# line_kick.net
KiCad netlist of a schematic drawn in EAGLE
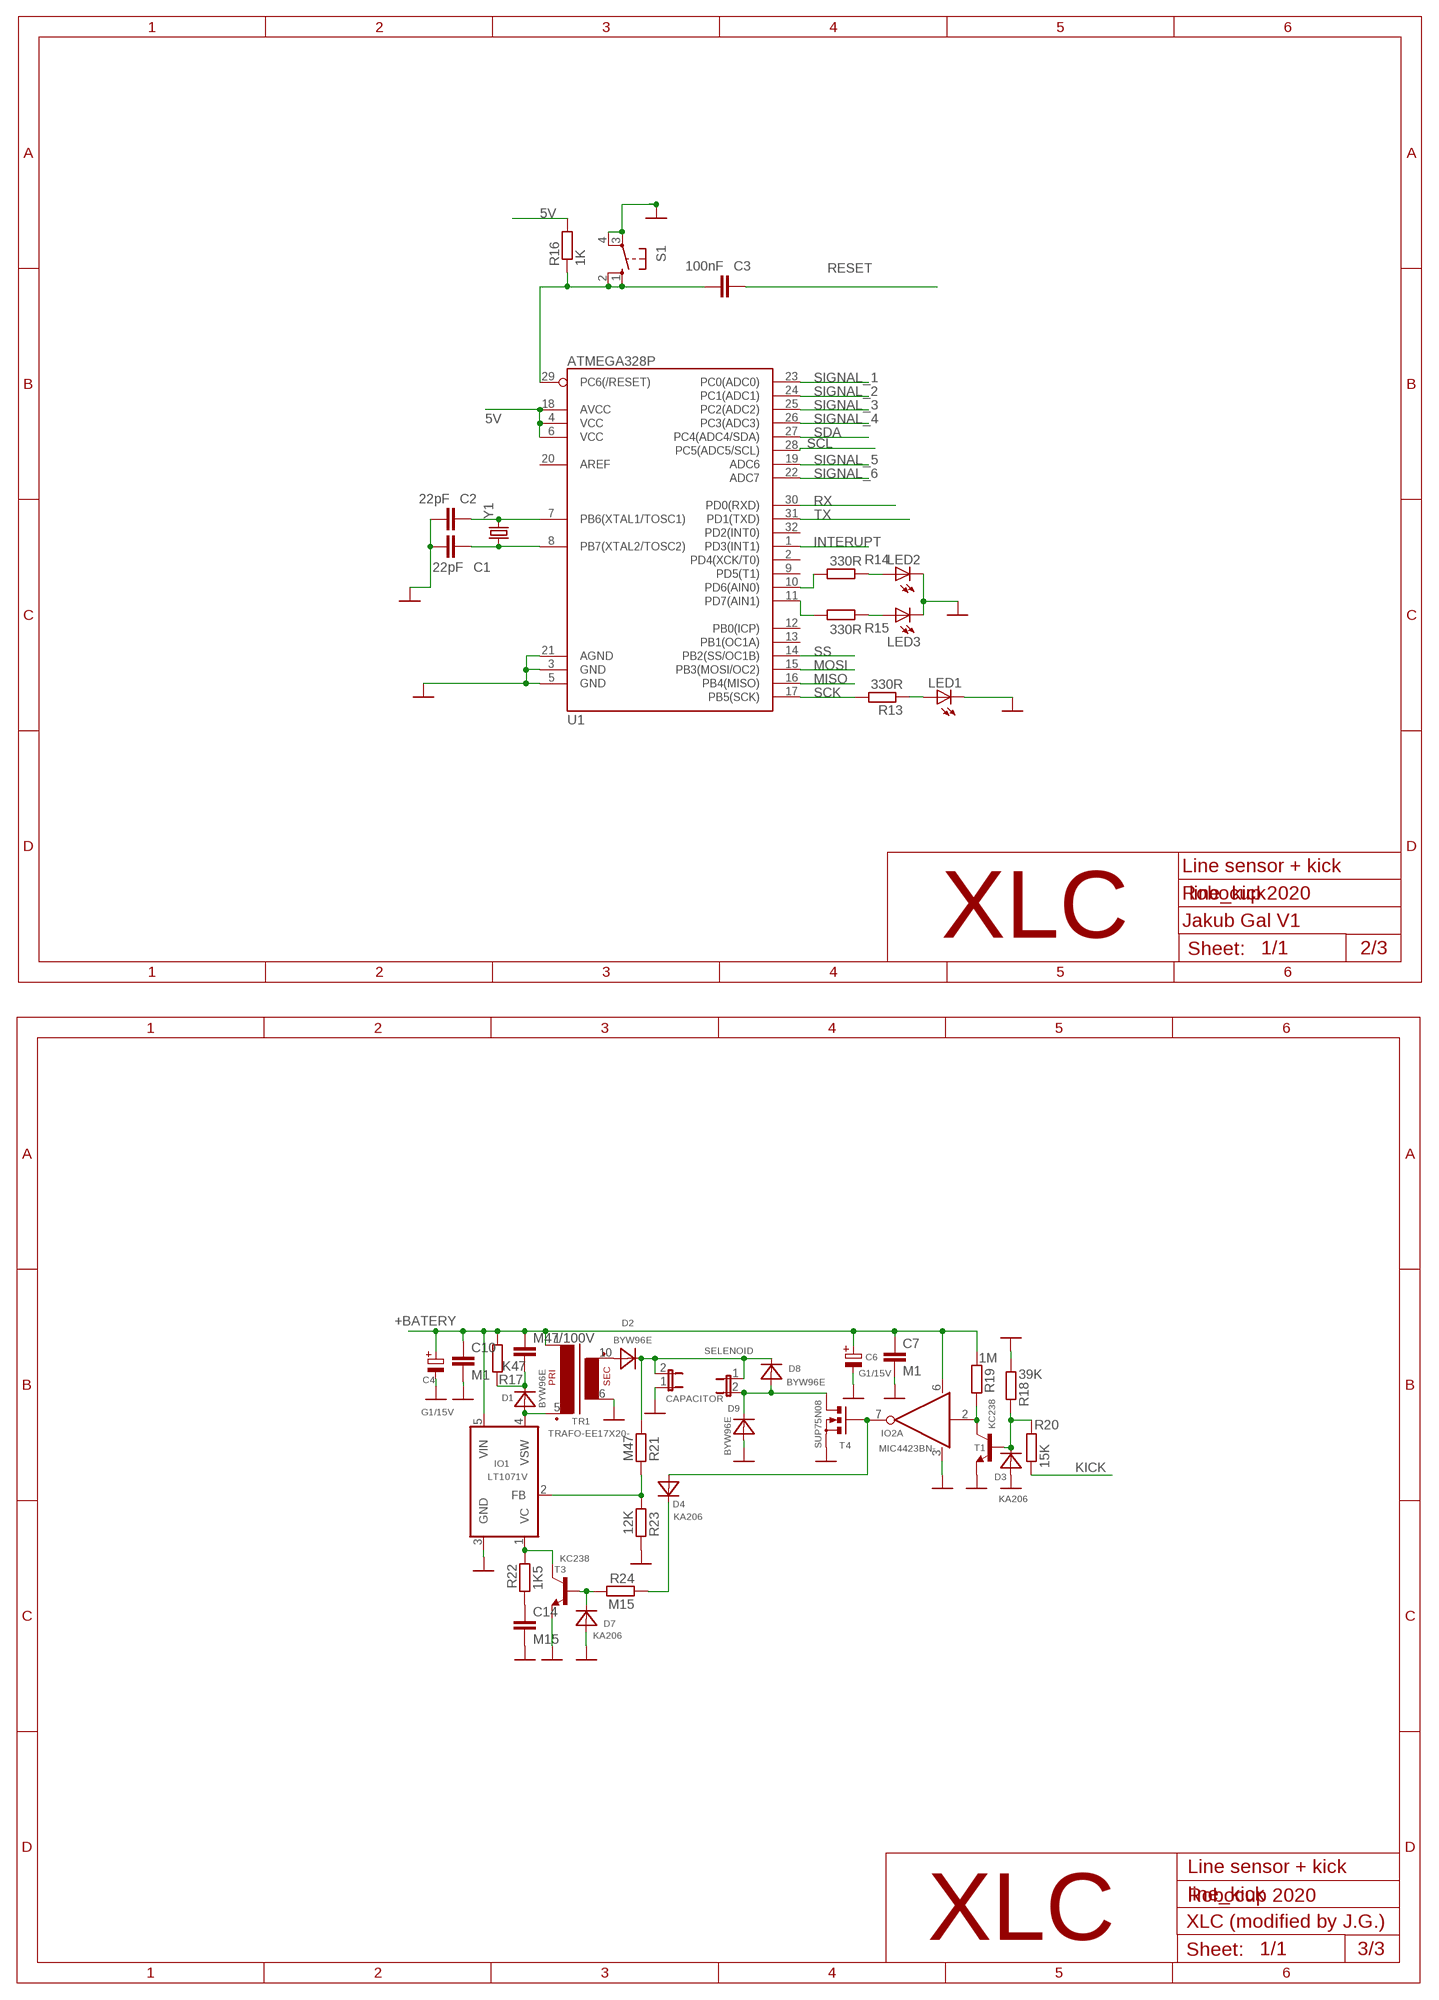
[diagram p0: schematic, sheet 1, part 1 of 2]
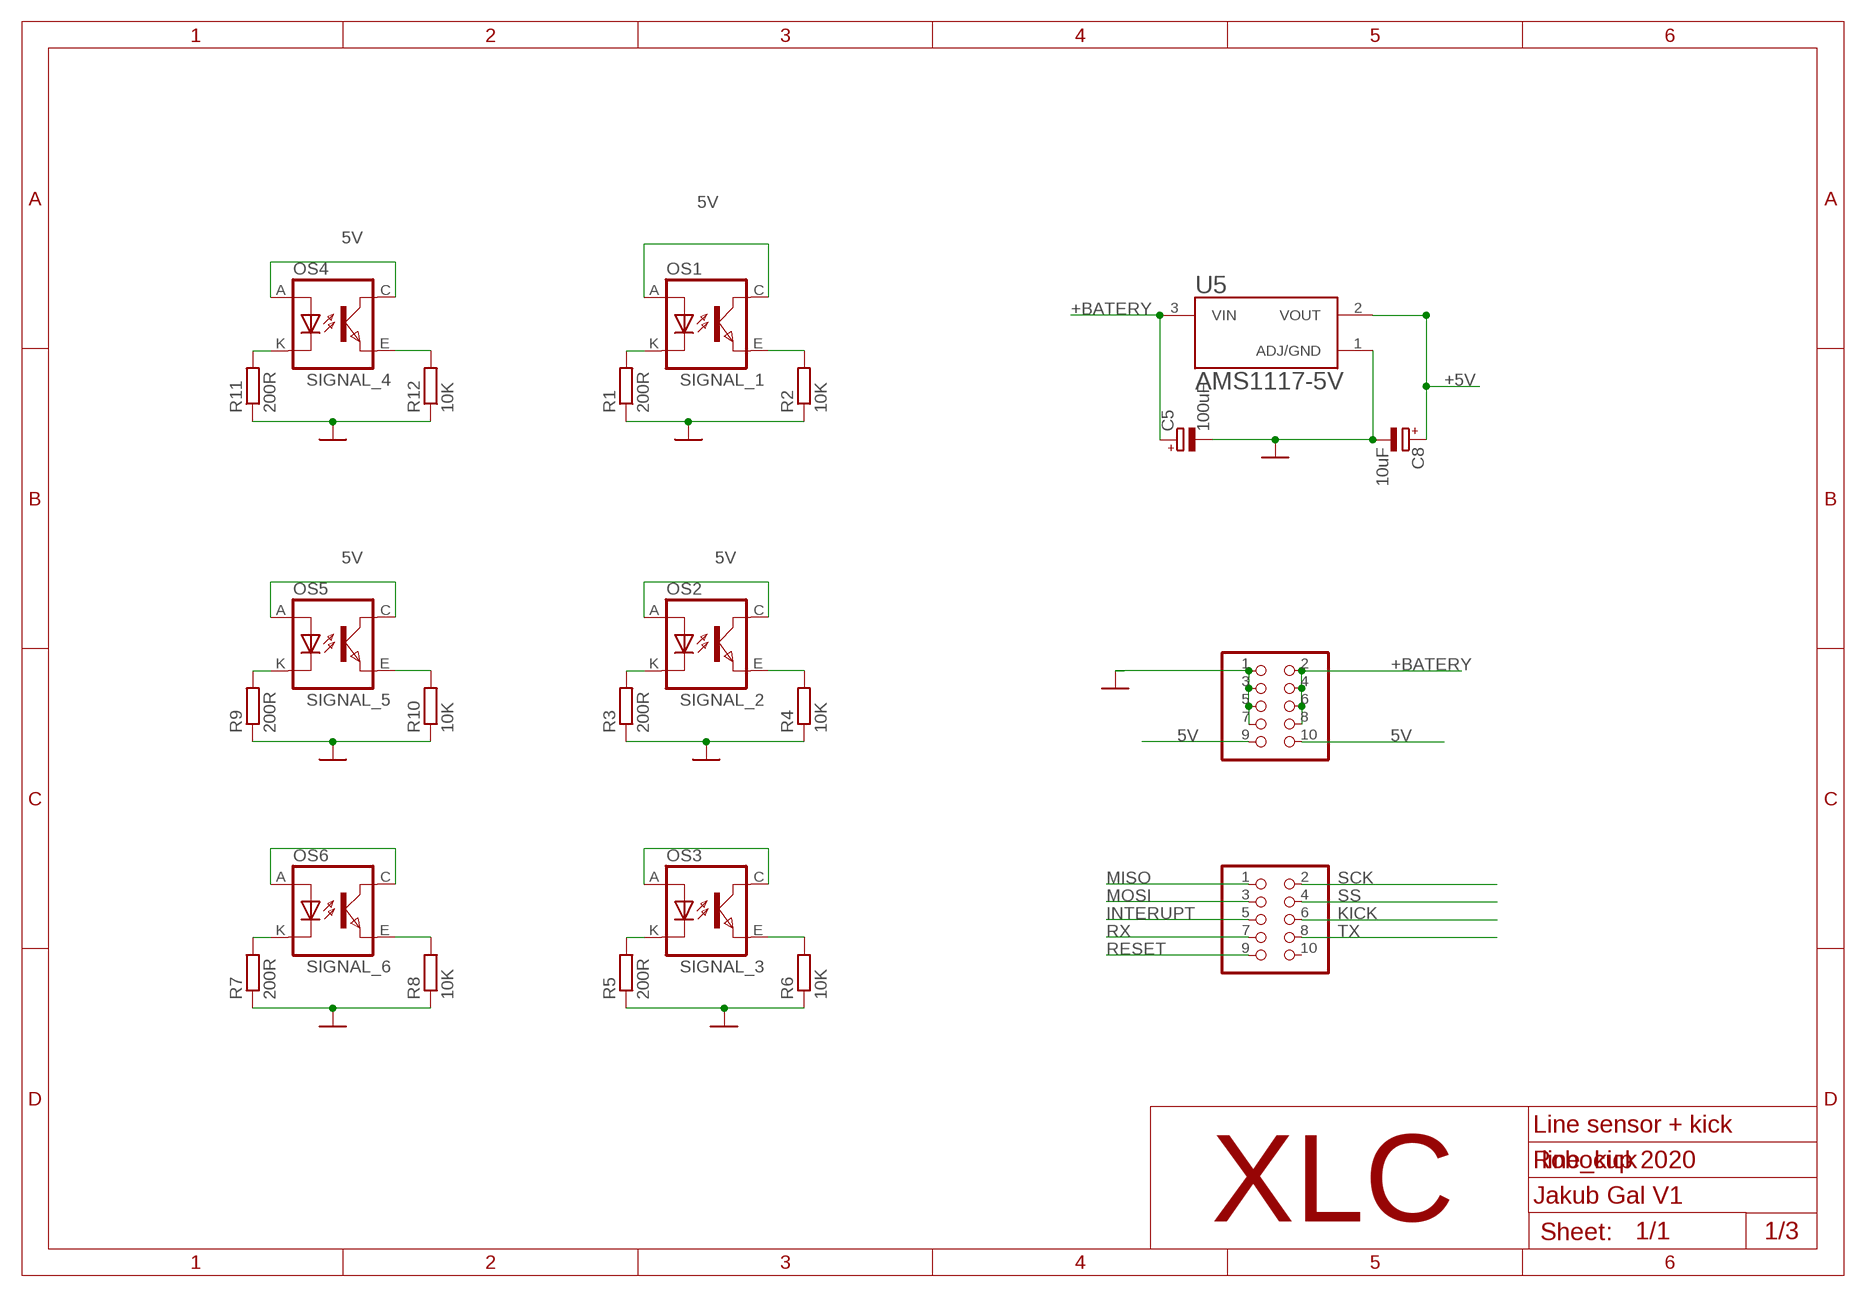
[diagram p1: schematic, sheet 1, part 2 of 2]

(export (version "E")
  (design (tool "Eeschema 10.0.6"))
  (components
    (comp (ref "C1")
      (value "22pF")
      (footprint "eagle-import:C0603")
      (libsource (lib "eagle-import") (part "C-EUC0603"))
    )
    (comp (ref "C2")
      (value "22pF")
      (footprint "eagle-import:C0603")
      (libsource (lib "eagle-import") (part "C-EUC0603"))
    )
    (comp (ref "C3")
      (value "100nF")
      (footprint "eagle-import:C0603")
      (libsource (lib "eagle-import") (part "C-EUC0603"))
    )
    (comp (ref "C4")
      (value "G1/15V")
      (footprint "eagle-import:E-2,5_7-RAD")
      (libsource (lib "eagle-import") (part "KOND-ELEKT-2,5/7"))
    )
    (comp (ref "C5")
      (value "100uF")
      (footprint "eagle-import:UD-6,3X7,7_NICHICON")
      (libsource (lib "eagle-import") (part "CPOL-EUUD-6,3X7,7"))
    )
    (comp (ref "C6")
      (value "G1/15V")
      (footprint "eagle-import:E-2,5_7-RAD")
      (libsource (lib "eagle-import") (part "KOND-ELEKT-2,5/7"))
    )
    (comp (ref "C7")
      (value "M1")
      (footprint "eagle-import:C0805K")
      (libsource (lib "eagle-import") (part "resistor_348_C-EUC0805K"))
    )
    (comp (ref "C8")
      (value "10uF")
      (footprint "eagle-import:UD-4X5,8_NICHICON")
      (libsource (lib "eagle-import") (part "CPOL-EUUD-4X5,8"))
    )
    (comp (ref "C10")
      (value "M1")
      (footprint "eagle-import:C0805K")
      (libsource (lib "eagle-import") (part "resistor_348_C-EUC0805K"))
    )
    (comp (ref "C14")
      (value "M15")
      (footprint "eagle-import:C0805K")
      (libsource (lib "eagle-import") (part "resistor_348_C-EUC0805K"))
    )
    (comp (ref "CAPACITOR")
      (value "JP2EN")
      (footprint "eagle-import:JP2E")
      (libsource (lib "eagle-import") (part "JP2EN"))
    )
    (comp (ref "D1")
      (value "BYW96E")
      (footprint "eagle-import:D-10")
      (libsource (lib "eagle-import") (part "DIODA-10MM"))
    )
    (comp (ref "D2")
      (value "BYW96E")
      (footprint "eagle-import:D-10")
      (libsource (lib "eagle-import") (part "DIODA-10MM"))
    )
    (comp (ref "D3")
      (value "KA206")
      (footprint "eagle-import:D-7,5")
      (libsource (lib "eagle-import") (part "DIODA-7,5MM"))
    )
    (comp (ref "D4")
      (value "KA206")
      (footprint "eagle-import:D-7,5")
      (libsource (lib "eagle-import") (part "DIODA-7,5MM"))
    )
    (comp (ref "D7")
      (value "KA206")
      (footprint "eagle-import:D-7,5")
      (libsource (lib "eagle-import") (part "DIODA-7,5MM"))
    )
    (comp (ref "D8")
      (value "BYW96E")
      (footprint "eagle-import:D-10")
      (libsource (lib "eagle-import") (part "DIODA-10MM"))
    )
    (comp (ref "D9")
      (value "BYW96E")
      (footprint "eagle-import:D-10")
      (libsource (lib "eagle-import") (part "DIODA-10MM"))
    )
    (comp (ref "IO1")
      (value "LT1071V")
      (footprint "eagle-import:TO-220-5P")
      (libsource (lib "eagle-import") (part "LT1071V"))
    )
    (comp (ref "IO2")
      (value "MIC4423BN-")
      (footprint "eagle-import:DIL8")
      (libsource (lib "eagle-import") (part "MIC4423BN-"))
    )
    (comp (ref "JP2")
      (value "PINHD-2X5")
      (footprint "eagle-import:2X05")
      (libsource (lib "eagle-import") (part "PINHD-2X5"))
    )
    (comp (ref "JP3")
      (value "PINHD-2X5")
      (footprint "eagle-import:2X05")
      (libsource (lib "eagle-import") (part "PINHD-2X5"))
    )
    (comp (ref "LED1")
      (value "LEDCHIPLED_0603")
      (footprint "eagle-import:CHIPLED_0603")
      (libsource (lib "eagle-import") (part "LEDCHIPLED_0603"))
    )
    (comp (ref "LED2")
      (value "LEDCHIPLED_0603")
      (footprint "eagle-import:CHIPLED_0603")
      (libsource (lib "eagle-import") (part "LEDCHIPLED_0603"))
    )
    (comp (ref "LED3")
      (value "LEDCHIPLED_0603")
      (footprint "eagle-import:CHIPLED_0603")
      (libsource (lib "eagle-import") (part "LEDCHIPLED_0603"))
    )
    (comp (ref "M47/100V")
      (value "C-EUC0805K")
      (footprint "eagle-import:C0805K")
      (libsource (lib "eagle-import") (part "resistor_348_C-EUC0805K"))
    )
    (comp (ref "OS1")
      (value "TCRT5000")
      (footprint "eagle-import:TCRT5000")
      (libsource (lib "eagle-import") (part "TCRT5000"))
    )
    (comp (ref "OS2")
      (value "TCRT5000")
      (footprint "eagle-import:TCRT5000")
      (libsource (lib "eagle-import") (part "TCRT5000"))
    )
    (comp (ref "OS3")
      (value "TCRT5000")
      (footprint "eagle-import:TCRT5000")
      (libsource (lib "eagle-import") (part "TCRT5000"))
    )
    (comp (ref "OS4")
      (value "TCRT5000")
      (footprint "eagle-import:TCRT5000")
      (fields (field (name "SPICEPREFIX") "O"))
      (libsource (lib "eagle-import") (part "TCRT5000"))
    )
    (comp (ref "OS5")
      (value "TCRT5000")
      (footprint "eagle-import:TCRT5000")
      (libsource (lib "eagle-import") (part "TCRT5000"))
    )
    (comp (ref "OS6")
      (value "TCRT5000")
      (footprint "eagle-import:TCRT5000")
      (fields (field (name "SPICEPREFIX") "O"))
      (libsource (lib "eagle-import") (part "TCRT5000"))
    )
    (comp (ref "R1")
      (value "200R")
      (footprint "eagle-import:R0603")
      (libsource (lib "eagle-import") (part "R-EU_R0603"))
    )
    (comp (ref "R2")
      (value "10K")
      (footprint "eagle-import:R0603")
      (libsource (lib "eagle-import") (part "R-EU_R0603"))
    )
    (comp (ref "R3")
      (value "200R")
      (footprint "eagle-import:R0603")
      (libsource (lib "eagle-import") (part "R-EU_R0603"))
    )
    (comp (ref "R4")
      (value "10K")
      (footprint "eagle-import:R0603")
      (libsource (lib "eagle-import") (part "R-EU_R0603"))
    )
    (comp (ref "R5")
      (value "200R")
      (footprint "eagle-import:R0603")
      (libsource (lib "eagle-import") (part "R-EU_R0603"))
    )
    (comp (ref "R6")
      (value "10K")
      (footprint "eagle-import:R0603")
      (libsource (lib "eagle-import") (part "R-EU_R0603"))
    )
    (comp (ref "R7")
      (value "200R")
      (footprint "eagle-import:R0603")
      (libsource (lib "eagle-import") (part "R-EU_R0603"))
    )
    (comp (ref "R8")
      (value "10K")
      (footprint "eagle-import:R0603")
      (libsource (lib "eagle-import") (part "R-EU_R0603"))
    )
    (comp (ref "R9")
      (value "200R")
      (footprint "eagle-import:R0603")
      (libsource (lib "eagle-import") (part "R-EU_R0603"))
    )
    (comp (ref "R10")
      (value "10K")
      (footprint "eagle-import:R0603")
      (libsource (lib "eagle-import") (part "R-EU_R0603"))
    )
    (comp (ref "R11")
      (value "200R")
      (footprint "eagle-import:R0603")
      (libsource (lib "eagle-import") (part "R-EU_R0603"))
    )
    (comp (ref "R12")
      (value "10K")
      (footprint "eagle-import:R0603")
      (libsource (lib "eagle-import") (part "R-EU_R0603"))
    )
    (comp (ref "R13")
      (value "330R")
      (footprint "eagle-import:R0603")
      (libsource (lib "eagle-import") (part "R-EU_R0603"))
    )
    (comp (ref "R14")
      (value "330R")
      (footprint "eagle-import:R0603")
      (libsource (lib "eagle-import") (part "R-EU_R0603"))
    )
    (comp (ref "R15")
      (value "330R")
      (footprint "eagle-import:R0603")
      (libsource (lib "eagle-import") (part "R-EU_R0603"))
    )
    (comp (ref "R16")
      (value "1K")
      (footprint "eagle-import:R0603")
      (libsource (lib "eagle-import") (part "R-EU_R0603"))
    )
    (comp (ref "R17")
      (value "K47")
      (footprint "eagle-import:R0603")
      (libsource (lib "eagle-import") (part "resistor_348_R-EU_R0603"))
    )
    (comp (ref "R18")
      (value "39K")
      (footprint "eagle-import:R0603")
      (libsource (lib "eagle-import") (part "resistor_348_R-EU_R0603"))
    )
    (comp (ref "R19")
      (value "1M")
      (footprint "eagle-import:R0603")
      (libsource (lib "eagle-import") (part "resistor_348_R-EU_R0603"))
    )
    (comp (ref "R20")
      (value "15K")
      (footprint "eagle-import:R0603")
      (libsource (lib "eagle-import") (part "resistor_348_R-EU_R0603"))
    )
    (comp (ref "R21")
      (value "M47")
      (footprint "eagle-import:R0603")
      (libsource (lib "eagle-import") (part "resistor_348_R-EU_R0603"))
    )
    (comp (ref "R22")
      (value "1K5")
      (footprint "eagle-import:R0603")
      (libsource (lib "eagle-import") (part "resistor_348_R-EU_R0603"))
    )
    (comp (ref "R23")
      (value "12K")
      (footprint "eagle-import:R0603")
      (libsource (lib "eagle-import") (part "resistor_348_R-EU_R0603"))
    )
    (comp (ref "R24")
      (value "M15")
      (footprint "eagle-import:R0603")
      (libsource (lib "eagle-import") (part "resistor_348_R-EU_R0603"))
    )
    (comp (ref "S1")
      (value "10-XX")
      (footprint "eagle-import:B3F-10XX")
      (fields (field (name "MPN") "B3F-1000"))
      (libsource (lib "eagle-import") (part "10-XX"))
    )
    (comp (ref "SELENOID")
      (value "JP2EN")
      (footprint "eagle-import:JP2E")
      (libsource (lib "eagle-import") (part "JP2EN"))
    )
    (comp (ref "T1")
      (value "KC238")
      (footprint "eagle-import:TO-92")
      (libsource (lib "eagle-import") (part "TRANZ-NPN-KC238-PLAST"))
    )
    (comp (ref "T3")
      (value "KC238")
      (footprint "eagle-import:TO-92")
      (libsource (lib "eagle-import") (part "TRANZ-NPN-KC238-PLAST"))
    )
    (comp (ref "T4")
      (value "SUP75N08")
      (footprint "eagle-import:TO-220")
      (libsource (lib "eagle-import") (part "BUZ90{dblquote}"))
    )
    (comp (ref "TR1")
      (value "TRAFO-EE17X20-")
      (footprint "eagle-import:TRAFO-EE17X20")
      (libsource (lib "eagle-import") (part "TRAFO-EE17X20-"))
    )
    (comp (ref "U1")
      (value "ATMEGA328P")
      (footprint "eagle-import:TQFP32-08")
      (libsource (lib "eagle-import") (part "ATMEGA328_SMT"))
    )
    (comp (ref "U5")
      (value "AMS1117-5V")
      (footprint "eagle-import:SOT229P700X180-4N")
      (fields (field (name "MF") "Advanced Monolithic Systems") (field (name "MP") "AMS1117-3.3"))
      (libsource (lib "eagle-import") (part "AMS1117-3.3"))
    )
    (comp (ref "Y1")
      (value "CRYSTALHC49US")
      (footprint "eagle-import:HC49US")
      (libsource (lib "eagle-import") (part "CRYSTALHC49US"))
    )
  )
  (nets
    (net (code "1") (name "/+5V") (class "Default")
      (node (ref "C8") (pin "+") (pinfunction "+_+") (pintype "passive"))
      (node (ref "U5") (pin "2") (pinfunction "VOUT_2") (pintype "output"))
    )
    (net (code "2") (name "/+BATERY") (class "Default")
      (node (ref "C10") (pin "1") (pinfunction "1_1") (pintype "passive"))
      (node (ref "C4") (pin "+") (pinfunction "+_+") (pintype "passive"))
      (node (ref "C5") (pin "+") (pinfunction "+_+") (pintype "passive"))
      (node (ref "C6") (pin "+") (pinfunction "+_+") (pintype "passive"))
      (node (ref "C7") (pin "1") (pinfunction "1_1") (pintype "passive"))
      (node (ref "IO1") (pin "5") (pinfunction "VIN_5") (pintype "power_in"))
      (node (ref "IO2") (pin "6") (pinfunction "VCC_6") (pintype "power_in"))
      (node (ref "JP3") (pin "2") (pinfunction "2_2") (pintype "passive"))
      (node (ref "JP3") (pin "4") (pinfunction "4_4") (pintype "passive"))
      (node (ref "JP3") (pin "6") (pinfunction "6_6") (pintype "passive"))
      (node (ref "JP3") (pin "8") (pinfunction "8_8") (pintype "passive"))
      (node (ref "M47/100V") (pin "1") (pinfunction "1_1") (pintype "passive"))
      (node (ref "R17") (pin "1") (pinfunction "1_1") (pintype "passive"))
      (node (ref "R19") (pin "2") (pinfunction "2_2") (pintype "passive"))
      (node (ref "TR1") (pin "1") (pinfunction "1_1") (pintype "passive"))
      (node (ref "U5") (pin "3") (pinfunction "VIN_3") (pintype "input"))
    )
    (net (code "3") (name "/5V") (class "Default")
      (node (ref "JP3") (pin "10") (pinfunction "10_10") (pintype "passive"))
      (node (ref "JP3") (pin "9") (pinfunction "9_9") (pintype "passive"))
      (node (ref "OS1") (pin "A") (pinfunction "ANODE_A") (pintype "passive"))
      (node (ref "OS1") (pin "C") (pinfunction "COLLECTOR_C") (pintype "passive"))
      (node (ref "OS2") (pin "A") (pinfunction "ANODE_A") (pintype "passive"))
      (node (ref "OS2") (pin "C") (pinfunction "COLLECTOR_C") (pintype "passive"))
      (node (ref "OS3") (pin "A") (pinfunction "ANODE_A") (pintype "passive"))
      (node (ref "OS3") (pin "C") (pinfunction "COLLECTOR_C") (pintype "passive"))
      (node (ref "OS4") (pin "A") (pinfunction "ANODE_A") (pintype "passive"))
      (node (ref "OS4") (pin "C") (pinfunction "COLLECTOR_C") (pintype "passive"))
      (node (ref "OS5") (pin "A") (pinfunction "ANODE_A") (pintype "passive"))
      (node (ref "OS5") (pin "C") (pinfunction "COLLECTOR_C") (pintype "passive"))
      (node (ref "OS6") (pin "A") (pinfunction "ANODE_A") (pintype "passive"))
      (node (ref "OS6") (pin "C") (pinfunction "COLLECTOR_C") (pintype "passive"))
      (node (ref "R16") (pin "2") (pinfunction "2_2") (pintype "passive"))
      (node (ref "U1") (pin "18") (pinfunction "AVCC_18") (pintype "bidirectional"))
      (node (ref "U1") (pin "4") (pinfunction "VCC_4") (pintype "bidirectional"))
      (node (ref "U1") (pin "6") (pinfunction "VCC_6") (pintype "bidirectional"))
    )
    (net (code "4") (name "/INTERUPT") (class "Default")
      (node (ref "JP2") (pin "5") (pinfunction "5_5") (pintype "passive"))
      (node (ref "U1") (pin "1") (pinfunction "PD3(INT1)_1") (pintype "bidirectional"))
    )
    (net (code "5") (name "/KICK") (class "Default")
      (node (ref "JP2") (pin "6") (pinfunction "6_6") (pintype "passive"))
      (node (ref "R20") (pin "1") (pinfunction "1_1") (pintype "passive"))
    )
    (net (code "6") (name "/MISO") (class "Default")
      (node (ref "JP2") (pin "1") (pinfunction "1_1") (pintype "passive"))
      (node (ref "U1") (pin "16") (pinfunction "PB4(MISO)_16") (pintype "bidirectional"))
    )
    (net (code "7") (name "/MOSI") (class "Default")
      (node (ref "JP2") (pin "3") (pinfunction "3_3") (pintype "passive"))
      (node (ref "U1") (pin "15") (pinfunction "PB3(MOSI/OC2)_15") (pintype "bidirectional"))
    )
    (net (code "8") (name "/RESET") (class "Default")
      (node (ref "C3") (pin "2") (pinfunction "2_2") (pintype "passive"))
      (node (ref "JP2") (pin "9") (pinfunction "9_9") (pintype "passive"))
    )
    (net (code "9") (name "/RX") (class "Default")
      (node (ref "JP2") (pin "7") (pinfunction "7_7") (pintype "passive"))
      (node (ref "U1") (pin "30") (pinfunction "PD0(RXD)_30") (pintype "bidirectional"))
    )
    (net (code "10") (name "/SCK") (class "Default")
      (node (ref "JP2") (pin "2") (pinfunction "2_2") (pintype "passive"))
      (node (ref "R13") (pin "2") (pinfunction "2_2") (pintype "passive"))
      (node (ref "U1") (pin "17") (pinfunction "PB5(SCK)_17") (pintype "bidirectional"))
    )
    (net (code "11") (name "/SCL") (class "Default")
      (node (ref "U1") (pin "28") (pinfunction "PC5(ADC5/SCL)_28") (pintype "bidirectional"))
    )
    (net (code "12") (name "/SDA") (class "Default")
      (node (ref "U1") (pin "27") (pinfunction "PC4(ADC4/SDA)_27") (pintype "bidirectional"))
    )
    (net (code "13") (name "/SIGNAL_1") (class "Default")
      (node (ref "OS1") (pin "E") (pinfunction "EMITTER_E") (pintype "passive"))
      (node (ref "R2") (pin "2") (pinfunction "2_2") (pintype "passive"))
      (node (ref "U1") (pin "23") (pinfunction "PC0(ADC0)_23") (pintype "bidirectional"))
    )
    (net (code "14") (name "/SIGNAL_2") (class "Default")
      (node (ref "OS2") (pin "E") (pinfunction "EMITTER_E") (pintype "passive"))
      (node (ref "R4") (pin "2") (pinfunction "2_2") (pintype "passive"))
      (node (ref "U1") (pin "24") (pinfunction "PC1(ADC1)_24") (pintype "bidirectional"))
    )
    (net (code "15") (name "/SIGNAL_3") (class "Default")
      (node (ref "OS3") (pin "E") (pinfunction "EMITTER_E") (pintype "passive"))
      (node (ref "R6") (pin "2") (pinfunction "2_2") (pintype "passive"))
      (node (ref "U1") (pin "25") (pinfunction "PC2(ADC2)_25") (pintype "bidirectional"))
    )
    (net (code "16") (name "/SIGNAL_4") (class "Default")
      (node (ref "OS4") (pin "E") (pinfunction "EMITTER_E") (pintype "passive"))
      (node (ref "R12") (pin "2") (pinfunction "2_2") (pintype "passive"))
      (node (ref "U1") (pin "26") (pinfunction "PC3(ADC3)_26") (pintype "bidirectional"))
    )
    (net (code "17") (name "/SIGNAL_5") (class "Default")
      (node (ref "OS5") (pin "E") (pinfunction "EMITTER_E") (pintype "passive"))
      (node (ref "R10") (pin "2") (pinfunction "2_2") (pintype "passive"))
      (node (ref "U1") (pin "19") (pinfunction "ADC6_19") (pintype "bidirectional"))
    )
    (net (code "18") (name "/SIGNAL_6") (class "Default")
      (node (ref "OS6") (pin "E") (pinfunction "EMITTER_E") (pintype "passive"))
      (node (ref "R8") (pin "2") (pinfunction "2_2") (pintype "passive"))
      (node (ref "U1") (pin "22") (pinfunction "ADC7_22") (pintype "bidirectional"))
    )
    (net (code "19") (name "/SS") (class "Default")
      (node (ref "JP2") (pin "4") (pinfunction "4_4") (pintype "passive"))
      (node (ref "U1") (pin "14") (pinfunction "PB2(SS/OC1B)_14") (pintype "bidirectional"))
    )
    (net (code "20") (name "/TX") (class "Default")
      (node (ref "JP2") (pin "8") (pinfunction "8_8") (pintype "passive"))
      (node (ref "U1") (pin "31") (pinfunction "PD1(TXD)_31") (pintype "bidirectional"))
    )
    (net (code "21") (name "GND") (class "Default")
      (node (ref "C1") (pin "1") (pinfunction "1_1") (pintype "passive"))
      (node (ref "C10") (pin "2") (pinfunction "2_2") (pintype "passive"))
      (node (ref "C14") (pin "2") (pinfunction "2_2") (pintype "passive"))
      (node (ref "C2") (pin "1") (pinfunction "1_1") (pintype "passive"))
      (node (ref "C4") (pin "-") (pinfunction "-_-") (pintype "passive"))
      (node (ref "C5") (pin "-") (pinfunction "-_-") (pintype "passive"))
      (node (ref "C6") (pin "-") (pinfunction "-_-") (pintype "passive"))
      (node (ref "C7") (pin "2") (pinfunction "2_2") (pintype "passive"))
      (node (ref "C8") (pin "-") (pinfunction "-_-") (pintype "passive"))
      (node (ref "CAPACITOR") (pin "1") (pinfunction "1_1") (pintype "passive"))
      (node (ref "D3") (pin "A") (pinfunction "A_A") (pintype "passive"))
      (node (ref "D7") (pin "A") (pinfunction "A_A") (pintype "passive"))
      (node (ref "D9") (pin "A") (pinfunction "A_A") (pintype "passive"))
      (node (ref "IO1") (pin "3") (pinfunction "GND_3") (pintype "power_in"))
      (node (ref "IO2") (pin "3") (pinfunction "GND_3") (pintype "power_in"))
      (node (ref "JP3") (pin "1") (pinfunction "1_1") (pintype "passive"))
      (node (ref "JP3") (pin "3") (pinfunction "3_3") (pintype "passive"))
      (node (ref "JP3") (pin "5") (pinfunction "5_5") (pintype "passive"))
      (node (ref "JP3") (pin "7") (pinfunction "7_7") (pintype "passive"))
      (node (ref "LED1") (pin "C") (pinfunction "C_C") (pintype "passive"))
      (node (ref "LED2") (pin "C") (pinfunction "C_C") (pintype "passive"))
      (node (ref "LED3") (pin "C") (pinfunction "C_C") (pintype "passive"))
      (node (ref "R1") (pin "1") (pinfunction "1_1") (pintype "passive"))
      (node (ref "R10") (pin "1") (pinfunction "1_1") (pintype "passive"))
      (node (ref "R11") (pin "1") (pinfunction "1_1") (pintype "passive"))
      (node (ref "R12") (pin "1") (pinfunction "1_1") (pintype "passive"))
      (node (ref "R18") (pin "2") (pinfunction "2_2") (pintype "passive"))
      (node (ref "R2") (pin "1") (pinfunction "1_1") (pintype "passive"))
      (node (ref "R23") (pin "1") (pinfunction "1_1") (pintype "passive"))
      (node (ref "R3") (pin "1") (pinfunction "1_1") (pintype "passive"))
      (node (ref "R4") (pin "1") (pinfunction "1_1") (pintype "passive"))
      (node (ref "R5") (pin "1") (pinfunction "1_1") (pintype "passive"))
      (node (ref "R6") (pin "1") (pinfunction "1_1") (pintype "passive"))
      (node (ref "R7") (pin "1") (pinfunction "1_1") (pintype "passive"))
      (node (ref "R8") (pin "1") (pinfunction "1_1") (pintype "passive"))
      (node (ref "R9") (pin "1") (pinfunction "1_1") (pintype "passive"))
      (node (ref "S1") (pin "3") (pinfunction "P_3") (pintype "passive"))
      (node (ref "S1") (pin "4") (pinfunction "P1_4") (pintype "passive"))
      (node (ref "T1") (pin "3") (pinfunction "E_3") (pintype "passive"))
      (node (ref "T3") (pin "3") (pinfunction "E_3") (pintype "passive"))
      (node (ref "T4") (pin "3") (pinfunction "S_3") (pintype "passive"))
      (node (ref "TR1") (pin "6") (pinfunction "3_6") (pintype "passive"))
      (node (ref "U1") (pin "21") (pinfunction "AGND_21") (pintype "bidirectional"))
      (node (ref "U1") (pin "3") (pinfunction "GND_3") (pintype "bidirectional"))
      (node (ref "U1") (pin "5") (pinfunction "GND_5") (pintype "bidirectional"))
      (node (ref "U5") (pin "1") (pinfunction "ADJ/GND_1") (pintype "power_in"))
    )
    (net (code "22") (name "Net-(C14-Pad1)") (class "Default")
      (node (ref "C14") (pin "1") (pinfunction "1_1") (pintype "passive"))
      (node (ref "R22") (pin "2") (pinfunction "2_2") (pintype "passive"))
    )
    (net (code "23") (name "Net-(CAPACITOR-Pad2)") (class "Default")
      (node (ref "CAPACITOR") (pin "2") (pinfunction "2_2") (pintype "passive"))
      (node (ref "D2") (pin "K") (pinfunction "K_K") (pintype "passive"))
      (node (ref "D8") (pin "K") (pinfunction "K_K") (pintype "passive"))
      (node (ref "R21") (pin "2") (pinfunction "2_2") (pintype "passive"))
      (node (ref "SELENOID") (pin "1") (pinfunction "1_1") (pintype "passive"))
    )
    (net (code "24") (name "Net-(D1-PadK)") (class "Default")
      (node (ref "D1") (pin "K") (pinfunction "K_K") (pintype "passive"))
      (node (ref "M47/100V") (pin "2") (pinfunction "2_2") (pintype "passive"))
      (node (ref "R17") (pin "2") (pinfunction "2_2") (pintype "passive"))
    )
    (net (code "25") (name "Net-(D4-PadK)") (class "Default")
      (node (ref "D4") (pin "K") (pinfunction "K_K") (pintype "passive"))
      (node (ref "R24") (pin "1") (pinfunction "1_1") (pintype "passive"))
    )
    (net (code "26") (name "Net-(IO1-FB)") (class "Default")
      (node (ref "IO1") (pin "2") (pinfunction "FB_2") (pintype "input"))
      (node (ref "R21") (pin "1") (pinfunction "1_1") (pintype "passive"))
      (node (ref "R23") (pin "2") (pinfunction "2_2") (pintype "passive"))
    )
    (net (code "27") (name "Net-(IO1-VC)") (class "Default")
      (node (ref "IO1") (pin "1") (pinfunction "VC_1") (pintype "input"))
      (node (ref "R22") (pin "1") (pinfunction "1_1") (pintype "passive"))
      (node (ref "T3") (pin "1") (pinfunction "C_1") (pintype "passive"))
    )
    (net (code "28") (name "Net-(IO1-VSW)") (class "Default")
      (node (ref "D1") (pin "A") (pinfunction "A_A") (pintype "passive"))
      (node (ref "IO1") (pin "4") (pinfunction "VSW_4") (pintype "output"))
      (node (ref "TR1") (pin "5") (pinfunction "2_5") (pintype "passive"))
    )
    (net (code "29") (name "Net-(IO2A-I)") (class "Default")
      (node (ref "IO2") (pin "2") (pinfunction "I_2") (pintype "input"))
      (node (ref "R19") (pin "1") (pinfunction "1_1") (pintype "passive"))
      (node (ref "T1") (pin "1") (pinfunction "C_1") (pintype "passive"))
    )
    (net (code "30") (name "Net-(IO2A-O)") (class "Default")
      (node (ref "D4") (pin "A") (pinfunction "A_A") (pintype "passive"))
      (node (ref "IO2") (pin "7") (pinfunction "O_7") (pintype "output"))
      (node (ref "T4") (pin "1") (pinfunction "G_1") (pintype "passive"))
    )
    (net (code "31") (name "Net-(LED1-PadA)") (class "Default")
      (node (ref "LED1") (pin "A") (pinfunction "A_A") (pintype "passive"))
      (node (ref "R13") (pin "1") (pinfunction "1_1") (pintype "passive"))
    )
    (net (code "32") (name "Net-(LED2-PadA)") (class "Default")
      (node (ref "LED2") (pin "A") (pinfunction "A_A") (pintype "passive"))
      (node (ref "R14") (pin "1") (pinfunction "1_1") (pintype "passive"))
    )
    (net (code "33") (name "Net-(LED3-PadA)") (class "Default")
      (node (ref "LED3") (pin "A") (pinfunction "A_A") (pintype "passive"))
      (node (ref "R15") (pin "1") (pinfunction "1_1") (pintype "passive"))
    )
    (net (code "34") (name "Net-(OS1-CATHODE)") (class "Default")
      (node (ref "OS1") (pin "K") (pinfunction "CATHODE_K") (pintype "passive"))
      (node (ref "R1") (pin "2") (pinfunction "2_2") (pintype "passive"))
    )
    (net (code "35") (name "Net-(OS2-CATHODE)") (class "Default")
      (node (ref "OS2") (pin "K") (pinfunction "CATHODE_K") (pintype "passive"))
      (node (ref "R3") (pin "2") (pinfunction "2_2") (pintype "passive"))
    )
    (net (code "36") (name "Net-(OS3-CATHODE)") (class "Default")
      (node (ref "OS3") (pin "K") (pinfunction "CATHODE_K") (pintype "passive"))
      (node (ref "R5") (pin "2") (pinfunction "2_2") (pintype "passive"))
    )
    (net (code "37") (name "Net-(OS4-CATHODE)") (class "Default")
      (node (ref "OS4") (pin "K") (pinfunction "CATHODE_K") (pintype "passive"))
      (node (ref "R11") (pin "2") (pinfunction "2_2") (pintype "passive"))
    )
    (net (code "38") (name "Net-(OS5-CATHODE)") (class "Default")
      (node (ref "OS5") (pin "K") (pinfunction "CATHODE_K") (pintype "passive"))
      (node (ref "R9") (pin "2") (pinfunction "2_2") (pintype "passive"))
    )
    (net (code "39") (name "Net-(OS6-CATHODE)") (class "Default")
      (node (ref "OS6") (pin "K") (pinfunction "CATHODE_K") (pintype "passive"))
      (node (ref "R7") (pin "2") (pinfunction "2_2") (pintype "passive"))
    )
    (net (code "40") (name "Net-(S1-S)") (class "Default")
      (node (ref "C3") (pin "1") (pinfunction "1_1") (pintype "passive"))
      (node (ref "R16") (pin "1") (pinfunction "1_1") (pintype "passive"))
      (node (ref "S1") (pin "1") (pinfunction "S_1") (pintype "passive"))
      (node (ref "S1") (pin "2") (pinfunction "S1_2") (pintype "passive"))
      (node (ref "U1") (pin "29") (pinfunction "PC6(/RESET)_29") (pintype "bidirectional"))
    )
    (net (code "41") (name "Net-(T1-B)") (class "Default")
      (node (ref "D3") (pin "K") (pinfunction "K_K") (pintype "passive"))
      (node (ref "R18") (pin "1") (pinfunction "1_1") (pintype "passive"))
      (node (ref "R20") (pin "2") (pinfunction "2_2") (pintype "passive"))
      (node (ref "T1") (pin "2") (pinfunction "B_2") (pintype "passive"))
    )
    (net (code "42") (name "Net-(T3-B)") (class "Default")
      (node (ref "D7") (pin "K") (pinfunction "K_K") (pintype "passive"))
      (node (ref "R24") (pin "2") (pinfunction "2_2") (pintype "passive"))
      (node (ref "T3") (pin "2") (pinfunction "B_2") (pintype "passive"))
    )
    (net (code "43") (name "Net-(T4-D)") (class "Default")
      (node (ref "D8") (pin "A") (pinfunction "A_A") (pintype "passive"))
      (node (ref "D9") (pin "K") (pinfunction "K_K") (pintype "passive"))
      (node (ref "SELENOID") (pin "2") (pinfunction "2_2") (pintype "passive"))
      (node (ref "T4") (pin "2") (pinfunction "D_2") (pintype "passive"))
    )
    (net (code "44") (name "Net-(TR1-4)") (class "Default")
      (node (ref "D2") (pin "A") (pinfunction "A_A") (pintype "passive"))
      (node (ref "TR1") (pin "10") (pinfunction "4_10") (pintype "passive"))
    )
    (net (code "45") (name "Net-(U1-PB6(XTAL1{slash}TOSC1))") (class "Default")
      (node (ref "C2") (pin "2") (pinfunction "2_2") (pintype "passive"))
      (node (ref "U1") (pin "7") (pinfunction "PB6(XTAL1/TOSC1)_7") (pintype "bidirectional"))
      (node (ref "Y1") (pin "2") (pinfunction "2_2") (pintype "passive"))
    )
    (net (code "46") (name "Net-(U1-PB7(XTAL2{slash}TOSC2))") (class "Default")
      (node (ref "C1") (pin "2") (pinfunction "2_2") (pintype "passive"))
      (node (ref "U1") (pin "8") (pinfunction "PB7(XTAL2/TOSC2)_8") (pintype "bidirectional"))
      (node (ref "Y1") (pin "1") (pinfunction "1_1") (pintype "passive"))
    )
    (net (code "47") (name "Net-(U1-PD6(AIN0))") (class "Default")
      (node (ref "R14") (pin "2") (pinfunction "2_2") (pintype "passive"))
      (node (ref "U1") (pin "10") (pinfunction "PD6(AIN0)_10") (pintype "bidirectional"))
    )
    (net (code "48") (name "Net-(U1-PD7(AIN1))") (class "Default")
      (node (ref "R15") (pin "2") (pinfunction "2_2") (pintype "passive"))
      (node (ref "U1") (pin "11") (pinfunction "PD7(AIN1)_11") (pintype "bidirectional"))
    )
    (net (code "49") (name "unconnected-(JP2-Pad10)") (class "Default")
      (node (ref "JP2") (pin "10") (pinfunction "10_10") (pintype "passive"))
    )
    (net (code "50") (name "unconnected-(U1-AREF-Pad20)") (class "Default")
      (node (ref "U1") (pin "20") (pinfunction "AREF_20") (pintype "bidirectional"))
    )
    (net (code "51") (name "unconnected-(U1-PB0(ICP)-Pad12)") (class "Default")
      (node (ref "U1") (pin "12") (pinfunction "PB0(ICP)_12") (pintype "bidirectional"))
    )
    (net (code "52") (name "unconnected-(U1-PB1(OC1A)-Pad13)") (class "Default")
      (node (ref "U1") (pin "13") (pinfunction "PB1(OC1A)_13") (pintype "bidirectional"))
    )
    (net (code "53") (name "unconnected-(U1-PD2(INT0)-Pad32)") (class "Default")
      (node (ref "U1") (pin "32") (pinfunction "PD2(INT0)_32") (pintype "bidirectional"))
    )
    (net (code "54") (name "unconnected-(U1-PD4(XCK{slash}T0)-Pad2)") (class "Default")
      (node (ref "U1") (pin "2") (pinfunction "PD4(XCK/T0)_2") (pintype "bidirectional"))
    )
    (net (code "55") (name "unconnected-(U1-PD5(T1)-Pad9)") (class "Default")
      (node (ref "U1") (pin "9") (pinfunction "PD5(T1)_9") (pintype "bidirectional"))
    )
  )
)
